# dev_board_v0_1.net
KiCad netlist of a schematic drawn in EAGLE
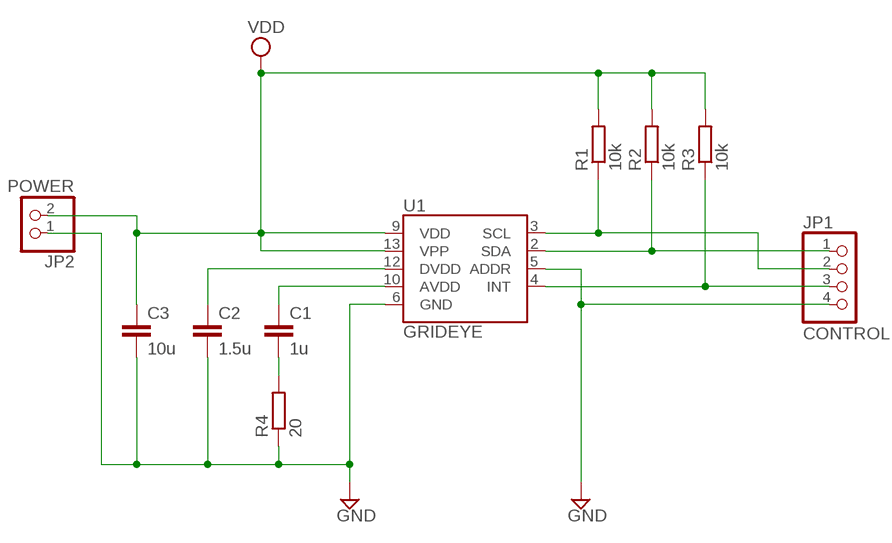
[diagram p0: schematic, sheet 1]

(export (version "E")
  (design (tool "Eeschema 10.0.6"))
  (components
    (comp (ref "C1")
      (value "1u")
      (footprint "eagle-import:C0805")
      (libsource (lib "eagle-import") (part "C-EUC0805"))
    )
    (comp (ref "C2")
      (value "1.5u")
      (footprint "eagle-import:C0805")
      (libsource (lib "eagle-import") (part "C-EUC0805"))
    )
    (comp (ref "C3")
      (value "10u")
      (footprint "eagle-import:C0805")
      (libsource (lib "eagle-import") (part "C-EUC0805"))
    )
    (comp (ref "JP1")
      (value "CONTROL")
      (footprint "eagle-import:1X04")
      (libsource (lib "eagle-import") (part "PINHD-1X4"))
    )
    (comp (ref "JP2")
      (value "POWER")
      (footprint "eagle-import:1X02")
      (libsource (lib "eagle-import") (part "PINHD-1X2"))
    )
    (comp (ref "R1")
      (value "10k")
      (footprint "eagle-import:R0805")
      (libsource (lib "eagle-import") (part "R-EU_R0805"))
    )
    (comp (ref "R2")
      (value "10k")
      (footprint "eagle-import:R0805")
      (libsource (lib "eagle-import") (part "R-EU_R0805"))
    )
    (comp (ref "R3")
      (value "10k")
      (footprint "eagle-import:R0805")
      (libsource (lib "eagle-import") (part "R-EU_R0805"))
    )
    (comp (ref "R4")
      (value "20")
      (footprint "eagle-import:R0805")
      (libsource (lib "eagle-import") (part "R-EU_R0805"))
    )
    (comp (ref "U1")
      (value "GRIDEYE")
      (footprint "eagle-import:GRIDEYE-AMG88")
      (libsource (lib "eagle-import") (part "GRIDEYE"))
    )
  )
  (nets
    (net (code "1") (name "GND") (class "Default")
      (node (ref "C2") (pin "2") (pinfunction "2_2") (pintype "passive"))
      (node (ref "C3") (pin "2") (pinfunction "2_2") (pintype "passive"))
      (node (ref "JP1") (pin "4") (pinfunction "4_4") (pintype "passive"))
      (node (ref "JP2") (pin "1") (pinfunction "1_1") (pintype "passive"))
      (node (ref "R4") (pin "1") (pinfunction "1_1") (pintype "passive"))
      (node (ref "U1") (pin "5") (pinfunction "ADDR_5") (pintype "bidirectional"))
      (node (ref "U1") (pin "6") (pinfunction "GND_6") (pintype "bidirectional"))
    )
    (net (code "2") (name "Net-(C1-Pad2)") (class "Default")
      (node (ref "C1") (pin "2") (pinfunction "2_2") (pintype "passive"))
      (node (ref "R4") (pin "2") (pinfunction "2_2") (pintype "passive"))
    )
    (net (code "3") (name "Net-(U1-AVDD)") (class "Default")
      (node (ref "C1") (pin "1") (pinfunction "1_1") (pintype "passive"))
      (node (ref "U1") (pin "10") (pinfunction "AVDD_10") (pintype "bidirectional"))
    )
    (net (code "4") (name "Net-(U1-DVDD)") (class "Default")
      (node (ref "C2") (pin "1") (pinfunction "1_1") (pintype "passive"))
      (node (ref "U1") (pin "12") (pinfunction "DVDD_12") (pintype "bidirectional"))
    )
    (net (code "5") (name "Net-(U1-INT)") (class "Default")
      (node (ref "JP1") (pin "3") (pinfunction "3_3") (pintype "passive"))
      (node (ref "R3") (pin "1") (pinfunction "1_1") (pintype "passive"))
      (node (ref "U1") (pin "4") (pinfunction "INT_4") (pintype "bidirectional"))
    )
    (net (code "6") (name "Net-(U1-SCL)") (class "Default")
      (node (ref "JP1") (pin "2") (pinfunction "2_2") (pintype "passive"))
      (node (ref "R1") (pin "1") (pinfunction "1_1") (pintype "passive"))
      (node (ref "U1") (pin "3") (pinfunction "SCL_3") (pintype "bidirectional"))
    )
    (net (code "7") (name "Net-(U1-SDA)") (class "Default")
      (node (ref "JP1") (pin "1") (pinfunction "1_1") (pintype "passive"))
      (node (ref "R2") (pin "1") (pinfunction "1_1") (pintype "passive"))
      (node (ref "U1") (pin "2") (pinfunction "SDA_2") (pintype "bidirectional"))
    )
    (net (code "8") (name "VDD") (class "Default")
      (node (ref "C3") (pin "1") (pinfunction "1_1") (pintype "passive"))
      (node (ref "JP2") (pin "2") (pinfunction "2_2") (pintype "passive"))
      (node (ref "R1") (pin "2") (pinfunction "2_2") (pintype "passive"))
      (node (ref "R2") (pin "2") (pinfunction "2_2") (pintype "passive"))
      (node (ref "R3") (pin "2") (pinfunction "2_2") (pintype "passive"))
      (node (ref "U1") (pin "13") (pinfunction "VPP_13") (pintype "bidirectional"))
      (node (ref "U1") (pin "9") (pinfunction "VDD_9") (pintype "bidirectional"))
    )
  )
)
